# lab10.net
KiCad netlist of a schematic drawn in Altium Designer
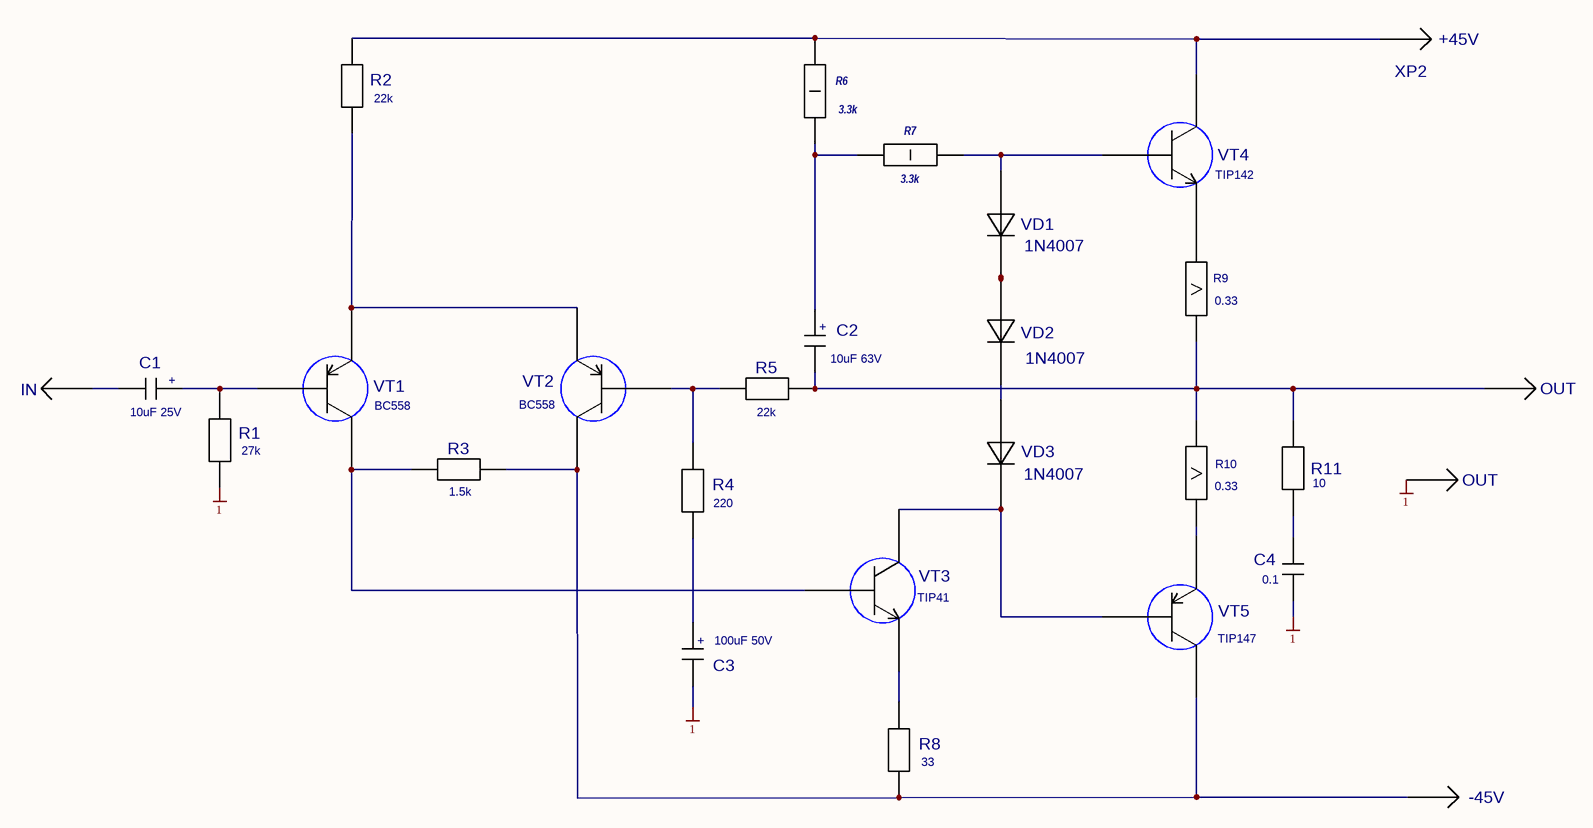
[diagram p0: lab10.SCHDOC]

(export (version "E")
  (design (tool "Eeschema 10.0.6"))
  (components
    (comp (ref "C1")
      (value "10uF 25V")
      (footprint "CAP2")
      (description "CAP2")
      (libsource (lib "*") (part "CAP2"))
    )
    (comp (ref "C2")
      (value "10uF 63V")
      (footprint "CAP2")
      (description "CAP2")
      (libsource (lib "*") (part "CAP2"))
    )
    (comp (ref "C3")
      (value "100uF 50V")
      (footprint "CAP2")
      (description "CAP2")
      (libsource (lib "*") (part "CAP2"))
    )
    (comp (ref "C4")
      (value "0.1")
      (footprint "CAP1")
      (description "CAP1")
      (libsource (lib "*") (part "CAP1"))
    )
    (comp (ref "R1") (value "27k") (footprint "RES") (description "RES") (libsource (lib "*") (part "RES")))
    (comp (ref "R2") (value "22k") (footprint "RES") (description "RES") (libsource (lib "*") (part "RES")))
    (comp (ref "R3") (value "1.5k") (footprint "RES") (description "RES") (libsource (lib "*") (part "RES")))
    (comp (ref "R4") (value "220") (footprint "RES") (description "RES") (libsource (lib "*") (part "RES")))
    (comp (ref "R5") (value "22k") (footprint "RES") (description "RES") (libsource (lib "*") (part "RES")))
    (comp (ref "R6")
      (value "3.3k")
      (footprint "МЛТ(1)")
      (description "МЛТ(1)")
      (libsource (lib "*") (part "МЛТ(1)"))
    )
    (comp (ref "R7")
      (value "3.3k")
      (footprint "МЛТ(1)")
      (description "МЛТ(1)")
      (libsource (lib "*") (part "МЛТ(1)"))
    )
    (comp (ref "R8") (value "33") (footprint "RES") (description "RES") (libsource (lib "*") (part "RES")))
    (comp (ref "R9")
      (value "0.33")
      (footprint "SQP5")
      (description "SQP5")
      (libsource (lib "*") (part "SQP5"))
    )
    (comp (ref "R10")
      (value "0.33")
      (footprint "SQP5")
      (description "SQP5")
      (libsource (lib "*") (part "SQP5"))
    )
    (comp (ref "R11") (value "10") (footprint "RES") (description "RES") (libsource (lib "*") (part "RES")))
    (comp (ref "VD1") (value "1N4007") (footprint "1N4007") (libsource (lib "*") (part "1N4007")))
    (comp (ref "VD2") (value "1N4007") (footprint "1N4007") (libsource (lib "*") (part "1N4007")))
    (comp (ref "VD3") (value "1N4007") (footprint "1N4007") (libsource (lib "*") (part "1N4007")))
    (comp (ref "VT1") (value "BC558") (footprint "BC558") (libsource (lib "*") (part "BC558")))
    (comp (ref "VT2") (value "BC558") (footprint "BC558") (libsource (lib "") (part "BC558_1")))
    (comp (ref "VT3") (value "TIP41") (footprint "TIP41") (libsource (lib "*") (part "TIP41")))
    (comp (ref "VT4") (value "TIP142") (footprint "TIP142") (libsource (lib "*") (part "TIP142")))
    (comp (ref "VT5") (value "TIP147") (footprint "TIP147") (libsource (lib "*") (part "TIP147")))
    (comp (ref "XP1") (value "IN") (footprint "PAD") (description "PAD") (libsource (lib "*") (part "PAD")))
    (comp (ref "XP2") (value "+45V") (footprint "PAD") (description "PAD") (libsource (lib "*") (part "PAD")))
    (comp (ref "XP3") (value "OUT") (footprint "PAD") (description "PAD") (libsource (lib "*") (part "PAD")))
    (comp (ref "XP4") (value "OUT") (footprint "PAD") (description "PAD") (libsource (lib "*") (part "PAD")))
    (comp (ref "XP5") (value "-45V") (footprint "PAD") (description "PAD") (libsource (lib "*") (part "PAD")))
  )
  (nets
    (net (code "1") (name "1") (class "Default")
      (node (ref "C3") (pin "2") (pinfunction "2_2") (pintype "passive"))
      (node (ref "C4") (pin "1") (pinfunction "1_1") (pintype "passive"))
      (node (ref "R1") (pin "1") (pinfunction "1_1") (pintype "passive"))
      (node (ref "XP4") (pin "1") (pinfunction "A1_1") (pintype "passive"))
    )
    (net (code "2") (name "Net-(C1-Pad1)") (class "Default")
      (node (ref "C1") (pin "1") (pinfunction "1_1") (pintype "passive"))
      (node (ref "R1") (pin "2") (pinfunction "2_2") (pintype "passive"))
      (node (ref "VT1") (pin "1") (pinfunction "1_1") (pintype "passive"))
    )
    (net (code "3") (name "Net-(C2-Pad1)") (class "Default")
      (node (ref "C2") (pin "1") (pinfunction "1_1") (pintype "passive"))
      (node (ref "R6") (pin "1") (pinfunction "1_1") (pintype "passive"))
      (node (ref "R7") (pin "2") (pinfunction "2_2") (pintype "passive"))
    )
    (net (code "4") (name "Net-(C3-Pad1)") (class "Default")
      (node (ref "C3") (pin "1") (pinfunction "1_1") (pintype "passive"))
      (node (ref "R4") (pin "1") (pinfunction "1_1") (pintype "passive"))
    )
    (net (code "5") (name "Net-(C4-Pad2)") (class "Default")
      (node (ref "C4") (pin "2") (pinfunction "2_2") (pintype "passive"))
      (node (ref "R11") (pin "1") (pinfunction "1_1") (pintype "passive"))
    )
    (net (code "6") (name "Net-(R2-Pad1)") (class "Default")
      (node (ref "R2") (pin "1") (pinfunction "1_1") (pintype "passive"))
      (node (ref "VT1") (pin "3") (pinfunction "3_3") (pintype "passive"))
      (node (ref "VT2") (pin "3") (pinfunction "3_3") (pintype "passive"))
    )
    (net (code "7") (name "Net-(R3-Pad2)") (class "Default")
      (node (ref "R3") (pin "2") (pinfunction "2_2") (pintype "passive"))
      (node (ref "VT1") (pin "2") (pinfunction "2_2") (pintype "passive"))
      (node (ref "VT3") (pin "1") (pinfunction "1_1") (pintype "passive"))
    )
    (net (code "8") (name "Net-(R4-Pad2)") (class "Default")
      (node (ref "R4") (pin "2") (pinfunction "2_2") (pintype "passive"))
      (node (ref "R5") (pin "2") (pinfunction "2_2") (pintype "passive"))
      (node (ref "VT2") (pin "1") (pinfunction "1_1") (pintype "passive"))
    )
    (net (code "9") (name "Net-(R8-Pad2)") (class "Default")
      (node (ref "R8") (pin "2") (pinfunction "2_2") (pintype "passive"))
      (node (ref "VT3") (pin "3") (pinfunction "3_3") (pintype "passive"))
    )
    (net (code "10") (name "Net-(R9-Pad2)") (class "Default")
      (node (ref "R9") (pin "2") (pinfunction "2_2") (pintype "passive"))
      (node (ref "VT4") (pin "3") (pinfunction "3_3") (pintype "passive"))
    )
    (net (code "11") (name "Net-(R10-Pad1)") (class "Default")
      (node (ref "R10") (pin "1") (pinfunction "1_1") (pintype "passive"))
      (node (ref "VT5") (pin "3") (pinfunction "3_3") (pintype "passive"))
    )
    (net (code "12") (name "Net-(VD1-A)") (class "Default")
      (node (ref "R7") (pin "1") (pinfunction "1_1") (pintype "passive"))
      (node (ref "VD1") (pin "2") (pinfunction "A_2") (pintype "passive"))
      (node (ref "VT4") (pin "1") (pinfunction "1_1") (pintype "passive"))
    )
    (net (code "13") (name "Net-(VD1-K)") (class "Default")
      (node (ref "VD1") (pin "1") (pinfunction "K_1") (pintype "passive"))
      (node (ref "VD2") (pin "2") (pinfunction "A_2") (pintype "passive"))
    )
    (net (code "14") (name "Net-(VD2-K)") (class "Default")
      (node (ref "VD2") (pin "1") (pinfunction "K_1") (pintype "passive"))
      (node (ref "VD3") (pin "2") (pinfunction "A_2") (pintype "passive"))
    )
    (net (code "15") (name "Net-(VD3-K)") (class "Default")
      (node (ref "VD3") (pin "1") (pinfunction "K_1") (pintype "passive"))
      (node (ref "VT3") (pin "2") (pinfunction "2_2") (pintype "passive"))
      (node (ref "VT5") (pin "1") (pinfunction "1_1") (pintype "passive"))
    )
    (net (code "16") (name "Net-(XP1-A1)") (class "Default")
      (node (ref "C1") (pin "2") (pinfunction "2_2") (pintype "passive"))
      (node (ref "XP1") (pin "1") (pinfunction "A1_1") (pintype "passive"))
    )
    (net (code "17") (name "Net-(XP2-A1)") (class "Default")
      (node (ref "R2") (pin "2") (pinfunction "2_2") (pintype "passive"))
      (node (ref "R6") (pin "2") (pinfunction "2_2") (pintype "passive"))
      (node (ref "VT4") (pin "2") (pinfunction "2_2") (pintype "passive"))
      (node (ref "XP2") (pin "1") (pinfunction "A1_1") (pintype "passive"))
    )
    (net (code "18") (name "Net-(XP3-A1)") (class "Default")
      (node (ref "C2") (pin "2") (pinfunction "2_2") (pintype "passive"))
      (node (ref "R10") (pin "2") (pinfunction "2_2") (pintype "passive"))
      (node (ref "R11") (pin "2") (pinfunction "2_2") (pintype "passive"))
      (node (ref "R5") (pin "1") (pinfunction "1_1") (pintype "passive"))
      (node (ref "R9") (pin "1") (pinfunction "1_1") (pintype "passive"))
      (node (ref "XP3") (pin "1") (pinfunction "A1_1") (pintype "passive"))
    )
    (net (code "19") (name "Net-(XP5-A1)") (class "Default")
      (node (ref "R3") (pin "1") (pinfunction "1_1") (pintype "passive"))
      (node (ref "R8") (pin "1") (pinfunction "1_1") (pintype "passive"))
      (node (ref "VT2") (pin "2") (pinfunction "2_2") (pintype "passive"))
      (node (ref "VT5") (pin "2") (pinfunction "2_2") (pintype "passive"))
      (node (ref "XP5") (pin "1") (pinfunction "A1_1") (pintype "passive"))
    )
  )
)
